# ProPrj_10MHzEOM_2025-06-26.net
KiCad netlist of a schematic drawn in EasyEDA Pro
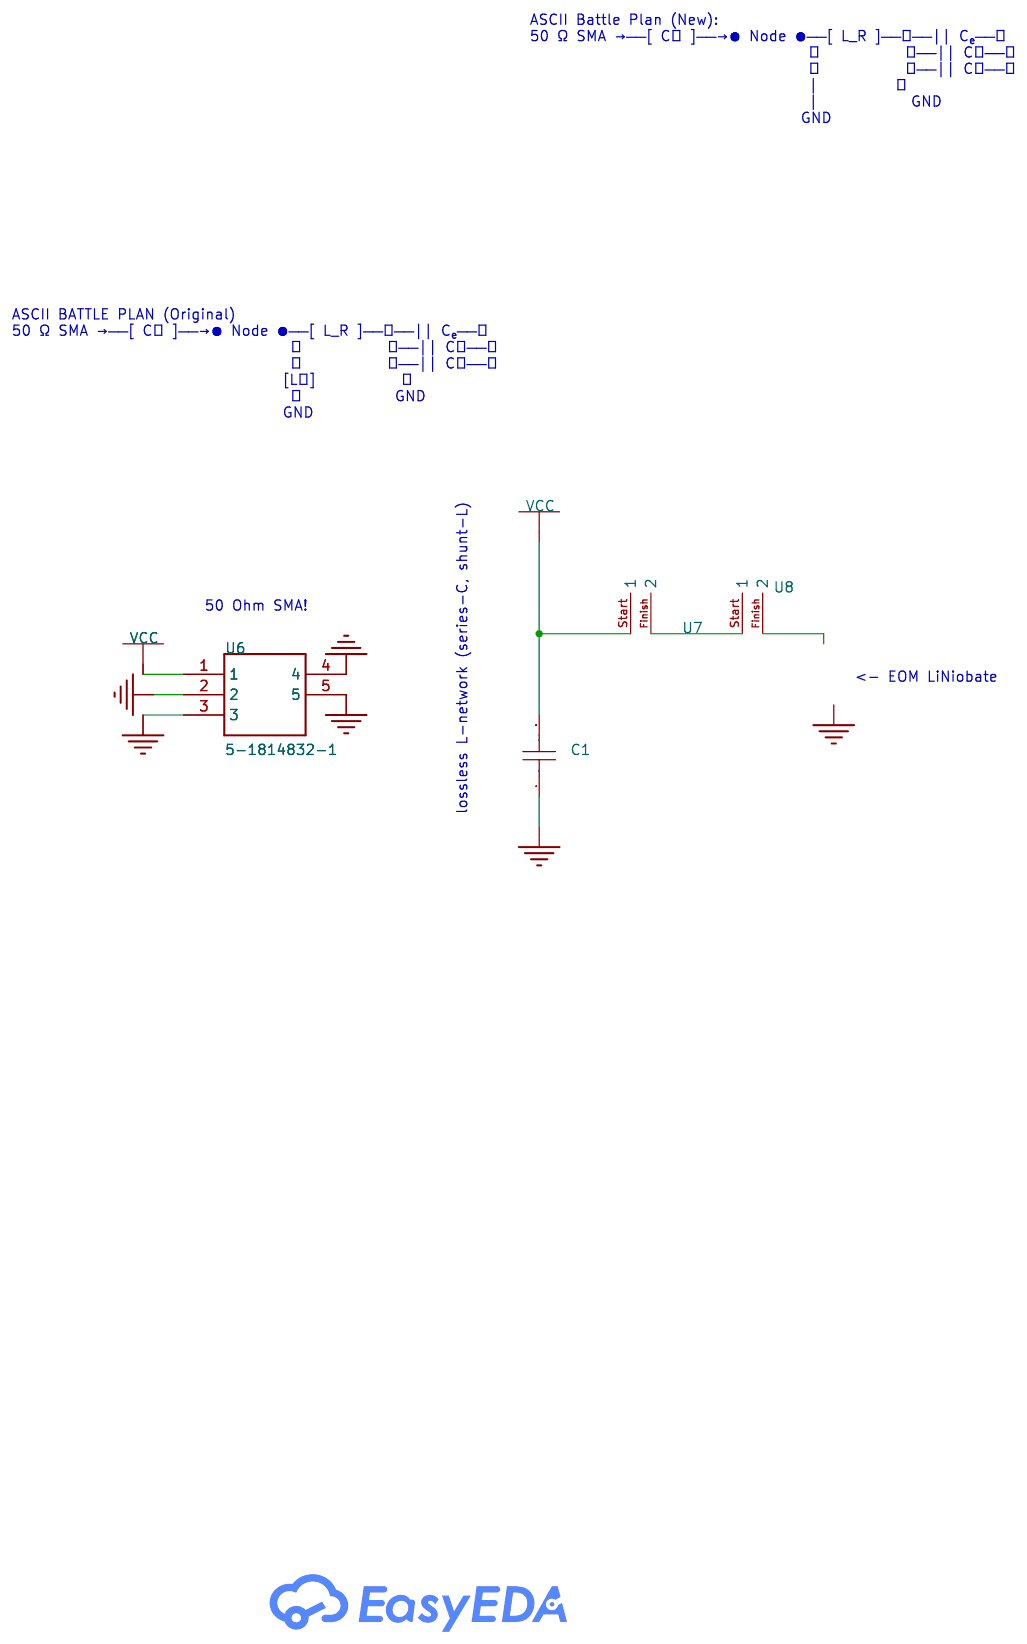
[diagram p0: schematic sheet]

(export (version "E")
  (design (tool "Eeschema 10.0.6"))
  (components
    (comp (ref "C1")
      (value "10nF")
      (footprint "easyedapro:C0805")
      (fields (field (name "Manufacturer Part") "0805B103K101NT") (field (name "Manufacturer") "FH(风华)"))
      (libsource (lib "easyedapro") (part "0805B103K101NT"))
    )
    (comp (ref "U6")
      (value "5-1814832-1")
      (footprint "easyedapro:5-1814832-1")
      (description "TSW-115-08-G-D-RA")
      (libsource (lib "easyedapro") (part "5-1814832-1"))
    )
    (comp (ref "U7")
      (value "~")
      (footprint "easyedapro:146-08J08L Adjustable")
      (libsource (lib "easyedapro") (part "146-08J08L Adjustable Inductor"))
    )
    (comp (ref "U8")
      (value "~")
      (footprint "easyedapro:1812CS-682")
      (description "1812CS-682")
      (libsource (lib "easyedapro") (part "1812CS-682"))
    )
  )
  (nets
    (net (code "1") (name "GND") (class "Default")
      (node (ref "C1") (pin "1") (pinfunction "1_1") (pintype "input"))
      (node (ref "U6") (pin "2") (pinfunction "2_2") (pintype "bidirectional"))
      (node (ref "U6") (pin "3") (pinfunction "3_3") (pintype "bidirectional"))
      (node (ref "U6") (pin "4") (pinfunction "4_4") (pintype "bidirectional"))
      (node (ref "U6") (pin "5") (pinfunction "5_5") (pintype "bidirectional"))
    )
    (net (code "2") (name "Net-(U7-2)") (class "Default")
      (node (ref "U7") (pin "Finish") (pinfunction "2_Finish") (pintype "input"))
      (node (ref "U8") (pin "Start") (pinfunction "1_Start") (pintype "input"))
    )
    (net (code "3") (name "VCC") (class "Default")
      (node (ref "C1") (pin "2") (pinfunction "2_2") (pintype "input"))
      (node (ref "U6") (pin "1") (pinfunction "1_1") (pintype "bidirectional"))
      (node (ref "U7") (pin "Start") (pinfunction "1_Start") (pintype "input"))
    )
    (net (code "4") (name "unconnected-(U8-2-PadFinish)") (class "Default")
      (node (ref "U8") (pin "Finish") (pinfunction "2_Finish") (pintype "input"))
    )
  )
)
